# W25Q32.net
KiCad netlist of a schematic drawn in Altium Designer
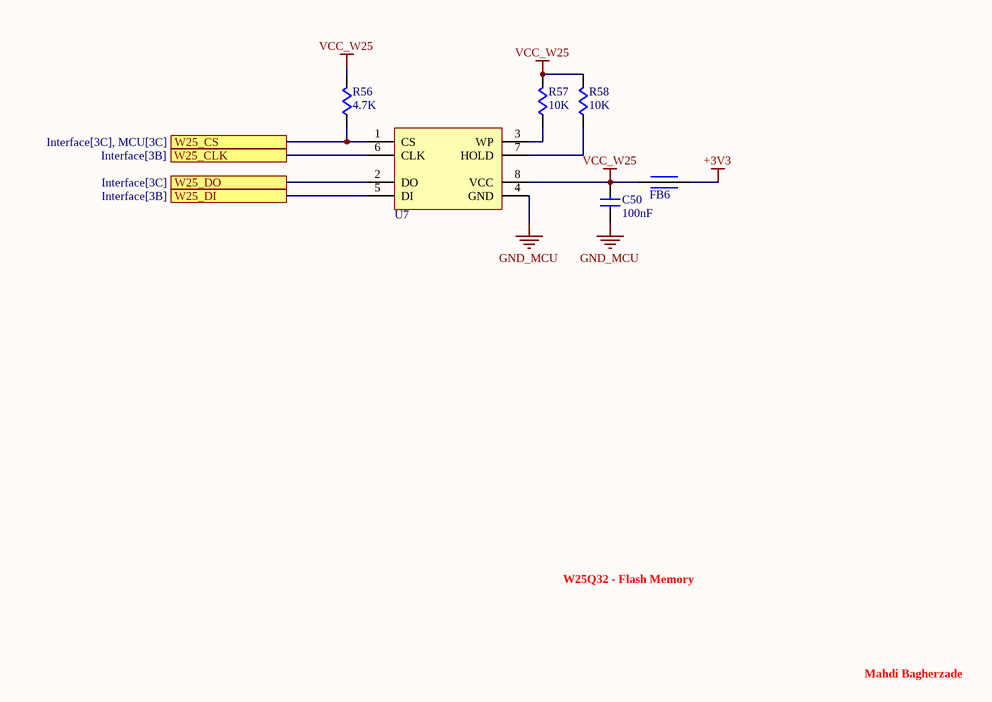
[diagram p0: W25Q32.SchDoc]

(export (version "E")
  (design (tool "Eeschema 10.0.6"))
  (components
    (comp (ref "C50")
      (value "100nF")
      (footprint "C-0805")
      (description "CAPACITOR")
      (fields
        (field (name "VOLTAGE") "50V")
        (field (name "TOLERANCE") "X7R")
        (field (name "PUBLISHER") "Mahdi Bagherzadeh")
      )
      (libsource (lib "Mahdi-Bagherzadeh") (part "CAP-CER"))
    )
    (comp (ref "FB6")
      (value "Ferrite Bead SMD")
      (footprint "FB-0805")
      (description "INDUCATOR")
      (fields (field (name "PUBLISHER") "Mahdi Bagherzadeh"))
      (libsource (lib "Mahdi-Bagherzadeh") (part "FERRITE BEAD"))
    )
    (comp (ref "R56")
      (value "4.7K")
      (footprint "R-0805")
      (description "RESISTOR")
      (fields
        (field (name "POWER") "1/8W")
        (field (name "TOLERANCE") "5%")
        (field (name "PUBLISHER") "Mahdi Bagherzadeh")
      )
      (libsource (lib "Mahdi-Bagherzadeh") (part "RES"))
    )
    (comp (ref "R57")
      (value "10K")
      (footprint "R-0805")
      (description "RESISTOR")
      (fields
        (field (name "POWER") "1/8W")
        (field (name "TOLERANCE") "5%")
        (field (name "PUBLISHER") "Mahdi Bagherzadeh")
      )
      (libsource (lib "Mahdi-Bagherzadeh") (part "RES"))
    )
    (comp (ref "R58")
      (value "10K")
      (footprint "R-0805")
      (description "RESISTOR")
      (fields
        (field (name "POWER") "1/8W")
        (field (name "TOLERANCE") "5%")
        (field (name "PUBLISHER") "Mahdi Bagherzadeh")
      )
      (libsource (lib "Mahdi-Bagherzadeh") (part "RES"))
    )
    (comp (ref "U7")
      (value "IC W25Qxx-SMD")
      (footprint "SOIC8-W")
      (description "IC")
      (fields (field (name "PUBLISHER") "Mahdi Bagherzadeh"))
      (libsource (lib "Mahdi-Bagherzadeh") (part "W25Qxx"))
    )
  )
  (nets
    (net (code "1") (name "+3V3") (class "Default")
      (node (ref "FB6") (pin "1") (pinfunction "1_1") (pintype "passive"))
    )
    (net (code "2") (name "/W25_CLK") (class "Default")
      (node (ref "U7") (pin "6") (pinfunction "CLK_6") (pintype "passive"))
    )
    (net (code "3") (name "/W25_CS") (class "Default")
      (node (ref "R56") (pin "1") (pinfunction "1_1") (pintype "passive"))
      (node (ref "U7") (pin "1") (pinfunction "CS_1") (pintype "passive"))
    )
    (net (code "4") (name "/W25_DI") (class "Default")
      (node (ref "U7") (pin "5") (pinfunction "DI_5") (pintype "passive"))
    )
    (net (code "5") (name "/W25_DO") (class "Default")
      (node (ref "U7") (pin "2") (pinfunction "DO_2") (pintype "passive"))
    )
    (net (code "6") (name "GND_MCU") (class "Default")
      (node (ref "C50") (pin "1") (pinfunction "1_1") (pintype "passive"))
      (node (ref "U7") (pin "4") (pinfunction "GND_4") (pintype "passive"))
    )
    (net (code "7") (name "Net-(U7-HOLD)") (class "Default")
      (node (ref "R58") (pin "1") (pinfunction "1_1") (pintype "passive"))
      (node (ref "U7") (pin "7") (pinfunction "HOLD_7") (pintype "passive"))
    )
    (net (code "8") (name "Net-(U7-WP)") (class "Default")
      (node (ref "R57") (pin "1") (pinfunction "1_1") (pintype "passive"))
      (node (ref "U7") (pin "3") (pinfunction "WP_3") (pintype "passive"))
    )
    (net (code "9") (name "VCC_W25") (class "Default")
      (node (ref "C50") (pin "2") (pinfunction "2_2") (pintype "passive"))
      (node (ref "FB6") (pin "2") (pinfunction "2_2") (pintype "passive"))
      (node (ref "R56") (pin "2") (pinfunction "2_2") (pintype "passive"))
      (node (ref "R57") (pin "2") (pinfunction "2_2") (pintype "passive"))
      (node (ref "R58") (pin "2") (pinfunction "2_2") (pintype "passive"))
      (node (ref "U7") (pin "8") (pinfunction "VCC_8") (pintype "passive"))
    )
  )
)
